# primary_DIO.net
KiCad netlist of a schematic drawn in Altium Designer
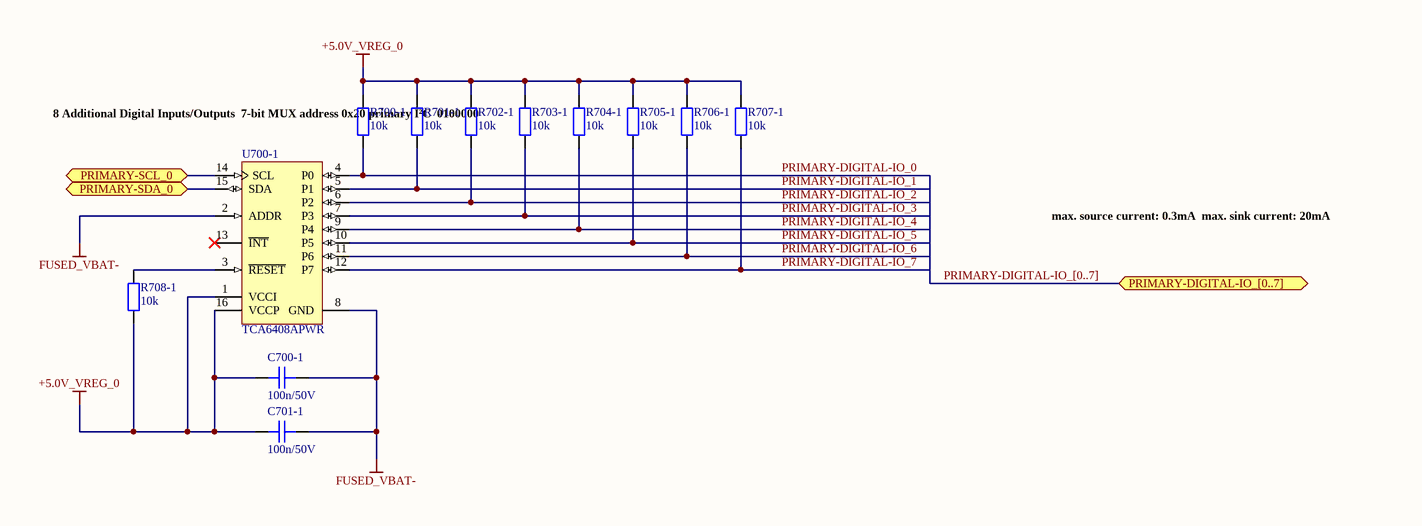
[diagram p0: primary_DIO.SchDoc]

(export (version "E")
  (design (tool "Eeschema 10.0.6"))
  (components
    (comp (ref "C700-1")
      (value "100n/50V")
      (footprint "CAPC1608X08N")
      (description "MLCC")
      (fields (field (name "PART NUMBER") "gen_C_ceramic_100n_50V_X7R_0603"))
      (libsource (lib "OE750") (part "C"))
    )
    (comp (ref "C701-1")
      (value "100n/50V")
      (footprint "CAPC1608X08N")
      (description "MLCC")
      (fields (field (name "PART NUMBER") "gen_C_ceramic_100n_50V_X7R_0603"))
      (libsource (lib "OE750") (part "C"))
    )
    (comp (ref "R700-1")
      (value "10k")
      (footprint "RESC1608X05N")
      (description "SMD Resistor 10k 0603")
      (fields (field (name "PART NUMBER") "gen_R_10k_0603") (field (name "TOLERANCE") "1%"))
      (libsource (lib "OE750") (part "R"))
    )
    (comp (ref "R701-1")
      (value "10k")
      (footprint "RESC1608X05N")
      (description "SMD Resistor 10k 0603")
      (fields (field (name "PART NUMBER") "gen_R_10k_0603") (field (name "TOLERANCE") "1%"))
      (libsource (lib "OE750") (part "R"))
    )
    (comp (ref "R702-1")
      (value "10k")
      (footprint "RESC1608X05N")
      (description "SMD Resistor 10k 0603")
      (fields (field (name "PART NUMBER") "gen_R_10k_0603") (field (name "TOLERANCE") "1%"))
      (libsource (lib "OE750") (part "R"))
    )
    (comp (ref "R703-1")
      (value "10k")
      (footprint "RESC1608X05N")
      (description "SMD Resistor 10k 0603")
      (fields (field (name "PART NUMBER") "gen_R_10k_0603") (field (name "TOLERANCE") "1%"))
      (libsource (lib "OE750") (part "R"))
    )
    (comp (ref "R704-1")
      (value "10k")
      (footprint "RESC1608X05N")
      (description "SMD Resistor 10k 0603")
      (fields (field (name "PART NUMBER") "gen_R_10k_0603") (field (name "TOLERANCE") "1%"))
      (libsource (lib "OE750") (part "R"))
    )
    (comp (ref "R705-1")
      (value "10k")
      (footprint "RESC1608X05N")
      (description "SMD Resistor 10k 0603")
      (fields (field (name "PART NUMBER") "gen_R_10k_0603") (field (name "TOLERANCE") "1%"))
      (libsource (lib "OE750") (part "R"))
    )
    (comp (ref "R706-1")
      (value "10k")
      (footprint "RESC1608X05N")
      (description "SMD Resistor 10k 0603")
      (fields (field (name "PART NUMBER") "gen_R_10k_0603") (field (name "TOLERANCE") "1%"))
      (libsource (lib "OE750") (part "R"))
    )
    (comp (ref "R707-1")
      (value "10k")
      (footprint "RESC1608X05N")
      (description "SMD Resistor 10k 0603")
      (fields (field (name "PART NUMBER") "gen_R_10k_0603") (field (name "TOLERANCE") "1%"))
      (libsource (lib "OE750") (part "R"))
    )
    (comp (ref "R708-1")
      (value "10k")
      (footprint "RESC1608X05N")
      (description "SMD Resistor 10k 0603")
      (fields (field (name "PART NUMBER") "gen_R_10k_0603") (field (name "TOLERANCE") "1%"))
      (libsource (lib "OE750") (part "R"))
    )
    (comp (ref "U700-1")
      (value "TCA6408APWR")
      (footprint "PW0016A_L")
      (fields (field (name "MANUFACTURER") "Texas Instruments"))
      (libsource (lib "Altium Content Vault") (part "TI-TCA6408A-TSSOP_PW-16"))
    )
  )
  (nets
    (net (code "1") (name "+5.0V_VREG_0") (class "Default")
      (node (ref "C700-1") (pin "2") (pinfunction "2_2") (pintype "passive"))
      (node (ref "C701-1") (pin "2") (pinfunction "2_2") (pintype "passive"))
      (node (ref "R700-1") (pin "2") (pinfunction "2_2") (pintype "passive"))
      (node (ref "R701-1") (pin "2") (pinfunction "2_2") (pintype "passive"))
      (node (ref "R702-1") (pin "2") (pinfunction "2_2") (pintype "passive"))
      (node (ref "R703-1") (pin "2") (pinfunction "2_2") (pintype "passive"))
      (node (ref "R704-1") (pin "2") (pinfunction "2_2") (pintype "passive"))
      (node (ref "R705-1") (pin "2") (pinfunction "2_2") (pintype "passive"))
      (node (ref "R706-1") (pin "2") (pinfunction "2_2") (pintype "passive"))
      (node (ref "R707-1") (pin "2") (pinfunction "2_2") (pintype "passive"))
      (node (ref "R708-1") (pin "1") (pinfunction "1_1") (pintype "passive"))
      (node (ref "U700-1") (pin "1") (pinfunction "VCCI_1") (pintype "power_in"))
      (node (ref "U700-1") (pin "16") (pinfunction "VCCP_16") (pintype "power_in"))
    )
    (net (code "2") (name "/PRIMARY-DIGITAL-IO_0") (class "Default")
      (node (ref "R700-1") (pin "1") (pinfunction "1_1") (pintype "passive"))
      (node (ref "U700-1") (pin "4") (pinfunction "P0_4") (pintype "bidirectional"))
    )
    (net (code "3") (name "/PRIMARY-DIGITAL-IO_1") (class "Default")
      (node (ref "R701-1") (pin "1") (pinfunction "1_1") (pintype "passive"))
      (node (ref "U700-1") (pin "5") (pinfunction "P1_5") (pintype "bidirectional"))
    )
    (net (code "4") (name "/PRIMARY-DIGITAL-IO_2") (class "Default")
      (node (ref "R702-1") (pin "1") (pinfunction "1_1") (pintype "passive"))
      (node (ref "U700-1") (pin "6") (pinfunction "P2_6") (pintype "bidirectional"))
    )
    (net (code "5") (name "/PRIMARY-DIGITAL-IO_3") (class "Default")
      (node (ref "R703-1") (pin "1") (pinfunction "1_1") (pintype "passive"))
      (node (ref "U700-1") (pin "7") (pinfunction "P3_7") (pintype "bidirectional"))
    )
    (net (code "6") (name "/PRIMARY-DIGITAL-IO_4") (class "Default")
      (node (ref "R704-1") (pin "1") (pinfunction "1_1") (pintype "passive"))
      (node (ref "U700-1") (pin "9") (pinfunction "P4_9") (pintype "bidirectional"))
    )
    (net (code "7") (name "/PRIMARY-DIGITAL-IO_5") (class "Default")
      (node (ref "R705-1") (pin "1") (pinfunction "1_1") (pintype "passive"))
      (node (ref "U700-1") (pin "10") (pinfunction "P5_10") (pintype "bidirectional"))
    )
    (net (code "8") (name "/PRIMARY-DIGITAL-IO_6") (class "Default")
      (node (ref "R706-1") (pin "1") (pinfunction "1_1") (pintype "passive"))
      (node (ref "U700-1") (pin "11") (pinfunction "P6_11") (pintype "bidirectional"))
    )
    (net (code "9") (name "/PRIMARY-DIGITAL-IO_7") (class "Default")
      (node (ref "R707-1") (pin "1") (pinfunction "1_1") (pintype "passive"))
      (node (ref "U700-1") (pin "12") (pinfunction "P7_12") (pintype "bidirectional"))
    )
    (net (code "11") (name "/PRIMARY-SCL_0") (class "Default")
      (node (ref "U700-1") (pin "14") (pinfunction "SCL_14") (pintype "input"))
    )
    (net (code "12") (name "/PRIMARY-SDA_0") (class "Default")
      (node (ref "U700-1") (pin "15") (pinfunction "SDA_15") (pintype "bidirectional"))
    )
    (net (code "13") (name "FUSED_VBAT-") (class "Default")
      (node (ref "C700-1") (pin "1") (pinfunction "1_1") (pintype "passive"))
      (node (ref "C701-1") (pin "1") (pinfunction "1_1") (pintype "passive"))
      (node (ref "U700-1") (pin "2") (pinfunction "ADDR_2") (pintype "input"))
      (node (ref "U700-1") (pin "8") (pinfunction "GND_8") (pintype "power_in"))
    )
    (net (code "14") (name "Net-(U700-1-~{RESET})") (class "Default")
      (node (ref "R708-1") (pin "2") (pinfunction "2_2") (pintype "passive"))
      (node (ref "U700-1") (pin "3") (pinfunction "~{RESET}_3") (pintype "input"))
    )
    (net (code "15") (name "unconnected-(U700-1-~{INT}-Pad13)") (class "Default")
      (node (ref "U700-1") (pin "13") (pinfunction "~{INT}_13") (pintype "open_collector+no_connect"))
    )
  )
)
